# SmartPlug.net
KiCad netlist of a schematic drawn in EAGLE
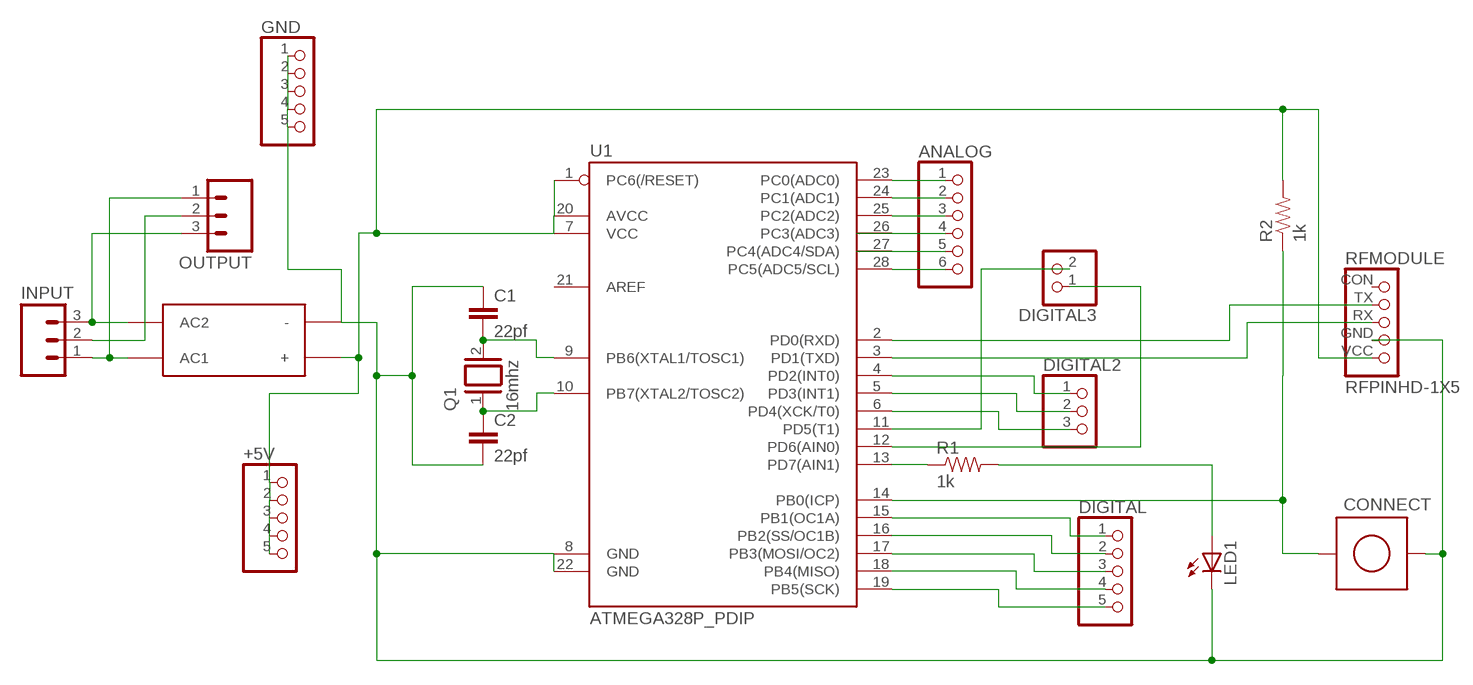
[diagram p0: schematic, sheet 1]

(export (version "E")
  (design (tool "Eeschema 10.0.6"))
  (components
    (comp (ref "+5V")
      (value "PINHD-1X5")
      (footprint "eagle-import:1X05")
      (libsource (lib "eagle-import") (part "PINHD-1X5"))
    )
    (comp (ref "ANALOG")
      (value "PINHD-1X6")
      (footprint "eagle-import:1X06")
      (libsource (lib "eagle-import") (part "PINHD-1X6"))
    )
    (comp (ref "C1")
      (value "22pf")
      (footprint "eagle-import:CAP-PTH-5MM")
      (libsource (lib "eagle-import") (part "CAPPTH1"))
    )
    (comp (ref "C2")
      (value "22pf")
      (footprint "eagle-import:CAP-PTH-5MM")
      (libsource (lib "eagle-import") (part "CAPPTH1"))
    )
    (comp (ref "CONNECT")
      (value "PUSHBUTTON6MM")
      (footprint "eagle-import:PUSHBUTTON6MM")
      (libsource (lib "eagle-import") (part "PUSHBUTTON6MM"))
    )
    (comp (ref "DIGITAL")
      (value "PINHD-1X5")
      (footprint "eagle-import:1X05")
      (libsource (lib "eagle-import") (part "PINHD-1X5"))
    )
    (comp (ref "DIGITAL2")
      (value "PINHD-1X3")
      (footprint "eagle-import:1X03")
      (libsource (lib "eagle-import") (part "PINHD-1X3"))
    )
    (comp (ref "DIGITAL3")
      (value "PINHD-1X2")
      (footprint "eagle-import:1X02")
      (libsource (lib "eagle-import") (part "PINHD-1X2"))
    )
    (comp (ref "GND")
      (value "PINHD-1X5")
      (footprint "eagle-import:1X05")
      (libsource (lib "eagle-import") (part "PINHD-1X5"))
    )
    (comp (ref "INPUT")
      (value "M03-SCREW-5MM")
      (footprint "eagle-import:SCREWTERMINAL-5MM-3")
      (libsource (lib "eagle-import") (part "M03-SCREW-5MM"))
    )
    (comp (ref "LED1")
      (value "LED3MM")
      (footprint "eagle-import:LED3MM")
      (libsource (lib "eagle-import") (part "LED3MM"))
    )
    (comp (ref "OUTPUT")
      (value "M03-SCREW-5MM")
      (footprint "eagle-import:SCREWTERMINAL-5MM-3")
      (libsource (lib "eagle-import") (part "M03-SCREW-5MM"))
    )
    (comp (ref "POWERMODULE")
      (value "POWER_MODULE")
      (footprint "eagle-import:POWER_MODULE")
      (libsource (lib "eagle-import") (part "POWER_MODULE"))
    )
    (comp (ref "Q1")
      (value "16mhz")
      (footprint "eagle-import:QS")
      (libsource (lib "eagle-import") (part "XTAL/S"))
    )
    (comp (ref "R1")
      (value "1k")
      (footprint "eagle-import:1_6W-RES")
      (libsource (lib "eagle-import") (part "RESISTORPTH-1/6W"))
    )
    (comp (ref "R2")
      (value "1k")
      (footprint "eagle-import:1_6W-RES")
      (libsource (lib "eagle-import") (part "RESISTORPTH-1/6W"))
    )
    (comp (ref "RFMODULE")
      (value "RFPINHD-1X5")
      (footprint "eagle-import:1X05")
      (libsource (lib "eagle-import") (part "RFPINHD-1X5"))
    )
    (comp (ref "U1")
      (value "ATMEGA328P_PDIP")
      (footprint "eagle-import:DIL28-3")
      (libsource (lib "eagle-import") (part "ATMEGA328P_PDIP"))
    )
  )
  (nets
    (net (code "1") (name "Net-(INPUT-Pad1)") (class "Default")
      (node (ref "INPUT") (pin "1") (pinfunction "1_1") (pintype "passive"))
      (node (ref "OUTPUT") (pin "1") (pinfunction "1_1") (pintype "passive"))
      (node (ref "POWERMODULE") (pin "AC1") (pinfunction "AC1_AC1") (pintype "bidirectional"))
    )
    (net (code "2") (name "Net-(INPUT-Pad2)") (class "Default")
      (node (ref "INPUT") (pin "2") (pinfunction "2_2") (pintype "passive"))
      (node (ref "OUTPUT") (pin "2") (pinfunction "2_2") (pintype "passive"))
    )
    (net (code "3") (name "Net-(INPUT-Pad3)") (class "Default")
      (node (ref "INPUT") (pin "3") (pinfunction "3_3") (pintype "passive"))
      (node (ref "OUTPUT") (pin "3") (pinfunction "3_3") (pintype "passive"))
      (node (ref "POWERMODULE") (pin "AC2") (pinfunction "AC2_AC2") (pintype "bidirectional"))
    )
    (net (code "4") (name "Net-(LED1-C)") (class "Default")
      (node (ref "C1") (pin "1") (pinfunction "1_1") (pintype "passive"))
      (node (ref "C2") (pin "2") (pinfunction "2_2") (pintype "passive"))
      (node (ref "CONNECT") (pin "P$2") (pinfunction "P$2_P$2") (pintype "output"))
      (node (ref "GND") (pin "1") (pinfunction "1_1") (pintype "passive"))
      (node (ref "GND") (pin "2") (pinfunction "2_2") (pintype "passive"))
      (node (ref "GND") (pin "3") (pinfunction "3_3") (pintype "passive"))
      (node (ref "GND") (pin "4") (pinfunction "4_4") (pintype "passive"))
      (node (ref "GND") (pin "5") (pinfunction "5_5") (pintype "passive"))
      (node (ref "LED1") (pin "K") (pinfunction "C_K") (pintype "passive"))
      (node (ref "POWERMODULE") (pin "-") (pinfunction "-_-") (pintype "bidirectional"))
      (node (ref "RFMODULE") (pin "GND") (pinfunction "4_GND") (pintype "passive"))
      (node (ref "U1") (pin "22") (pinfunction "GND_22") (pintype "bidirectional"))
      (node (ref "U1") (pin "8") (pinfunction "GND_8") (pintype "bidirectional"))
    )
    (net (code "5") (name "Net-(LED1-PadA)") (class "Default")
      (node (ref "LED1") (pin "A") (pinfunction "A_A") (pintype "passive"))
      (node (ref "R1") (pin "2") (pinfunction "2_2") (pintype "passive"))
    )
    (net (code "6") (name "Net-(RFMODULE-2)") (class "Default")
      (node (ref "RFMODULE") (pin "TX") (pinfunction "2_TX") (pintype "passive"))
      (node (ref "U1") (pin "2") (pinfunction "PD0(RXD)_2") (pintype "bidirectional"))
    )
    (net (code "7") (name "Net-(RFMODULE-3)") (class "Default")
      (node (ref "RFMODULE") (pin "RX") (pinfunction "3_RX") (pintype "passive"))
      (node (ref "U1") (pin "3") (pinfunction "PD1(TXD)_3") (pintype "bidirectional"))
    )
    (net (code "8") (name "Net-(RFMODULE-5)") (class "Default")
      (node (ref "+5V") (pin "1") (pinfunction "1_1") (pintype "passive"))
      (node (ref "+5V") (pin "2") (pinfunction "2_2") (pintype "passive"))
      (node (ref "+5V") (pin "3") (pinfunction "3_3") (pintype "passive"))
      (node (ref "+5V") (pin "4") (pinfunction "4_4") (pintype "passive"))
      (node (ref "+5V") (pin "5") (pinfunction "5_5") (pintype "passive"))
      (node (ref "POWERMODULE") (pin "+") (pinfunction "+_+") (pintype "bidirectional"))
      (node (ref "R2") (pin "2") (pinfunction "2_2") (pintype "passive"))
      (node (ref "RFMODULE") (pin "VCC") (pinfunction "5_VCC") (pintype "passive"))
      (node (ref "U1") (pin "1") (pinfunction "PC6(/RESET)_1") (pintype "bidirectional"))
      (node (ref "U1") (pin "20") (pinfunction "AVCC_20") (pintype "bidirectional"))
      (node (ref "U1") (pin "7") (pinfunction "VCC_7") (pintype "bidirectional"))
    )
    (net (code "9") (name "Net-(U1-PB0(ICP))") (class "Default")
      (node (ref "CONNECT") (pin "P$1") (pinfunction "P$1_P$1") (pintype "input"))
      (node (ref "R2") (pin "1") (pinfunction "1_1") (pintype "passive"))
      (node (ref "U1") (pin "14") (pinfunction "PB0(ICP)_14") (pintype "bidirectional"))
    )
    (net (code "10") (name "Net-(U1-PB1(OC1A))") (class "Default")
      (node (ref "DIGITAL") (pin "1") (pinfunction "1_1") (pintype "passive"))
      (node (ref "U1") (pin "15") (pinfunction "PB1(OC1A)_15") (pintype "bidirectional"))
    )
    (net (code "11") (name "Net-(U1-PB2(SS{slash}OC1B))") (class "Default")
      (node (ref "DIGITAL") (pin "2") (pinfunction "2_2") (pintype "passive"))
      (node (ref "U1") (pin "16") (pinfunction "PB2(SS/OC1B)_16") (pintype "bidirectional"))
    )
    (net (code "12") (name "Net-(U1-PB3(MOSI{slash}OC2))") (class "Default")
      (node (ref "DIGITAL") (pin "3") (pinfunction "3_3") (pintype "passive"))
      (node (ref "U1") (pin "17") (pinfunction "PB3(MOSI/OC2)_17") (pintype "bidirectional"))
    )
    (net (code "13") (name "Net-(U1-PB4(MISO))") (class "Default")
      (node (ref "DIGITAL") (pin "4") (pinfunction "4_4") (pintype "passive"))
      (node (ref "U1") (pin "18") (pinfunction "PB4(MISO)_18") (pintype "bidirectional"))
    )
    (net (code "14") (name "Net-(U1-PB5(SCK))") (class "Default")
      (node (ref "DIGITAL") (pin "5") (pinfunction "5_5") (pintype "passive"))
      (node (ref "U1") (pin "19") (pinfunction "PB5(SCK)_19") (pintype "bidirectional"))
    )
    (net (code "15") (name "Net-(U1-PB6(XTAL1{slash}TOSC1))") (class "Default")
      (node (ref "C1") (pin "2") (pinfunction "2_2") (pintype "passive"))
      (node (ref "Q1") (pin "2") (pinfunction "2_2") (pintype "passive"))
      (node (ref "U1") (pin "9") (pinfunction "PB6(XTAL1/TOSC1)_9") (pintype "bidirectional"))
    )
    (net (code "16") (name "Net-(U1-PB7(XTAL2{slash}TOSC2))") (class "Default")
      (node (ref "C2") (pin "1") (pinfunction "1_1") (pintype "passive"))
      (node (ref "Q1") (pin "1") (pinfunction "1_1") (pintype "passive"))
      (node (ref "U1") (pin "10") (pinfunction "PB7(XTAL2/TOSC2)_10") (pintype "bidirectional"))
    )
    (net (code "17") (name "Net-(U1-PC0(ADC0))") (class "Default")
      (node (ref "ANALOG") (pin "1") (pinfunction "1_1") (pintype "passive"))
      (node (ref "U1") (pin "23") (pinfunction "PC0(ADC0)_23") (pintype "bidirectional"))
    )
    (net (code "18") (name "Net-(U1-PC1(ADC1))") (class "Default")
      (node (ref "ANALOG") (pin "2") (pinfunction "2_2") (pintype "passive"))
      (node (ref "U1") (pin "24") (pinfunction "PC1(ADC1)_24") (pintype "bidirectional"))
    )
    (net (code "19") (name "Net-(U1-PC2(ADC2))") (class "Default")
      (node (ref "ANALOG") (pin "3") (pinfunction "3_3") (pintype "passive"))
      (node (ref "U1") (pin "25") (pinfunction "PC2(ADC2)_25") (pintype "bidirectional"))
    )
    (net (code "20") (name "Net-(U1-PC3(ADC3))") (class "Default")
      (node (ref "ANALOG") (pin "4") (pinfunction "4_4") (pintype "passive"))
      (node (ref "U1") (pin "26") (pinfunction "PC3(ADC3)_26") (pintype "bidirectional"))
    )
    (net (code "21") (name "Net-(U1-PC4(ADC4{slash}SDA))") (class "Default")
      (node (ref "ANALOG") (pin "5") (pinfunction "5_5") (pintype "passive"))
      (node (ref "U1") (pin "27") (pinfunction "PC4(ADC4/SDA)_27") (pintype "bidirectional"))
    )
    (net (code "22") (name "Net-(U1-PC5(ADC5{slash}SCL))") (class "Default")
      (node (ref "ANALOG") (pin "6") (pinfunction "6_6") (pintype "passive"))
      (node (ref "U1") (pin "28") (pinfunction "PC5(ADC5/SCL)_28") (pintype "bidirectional"))
    )
    (net (code "23") (name "Net-(U1-PD2(INT0))") (class "Default")
      (node (ref "DIGITAL2") (pin "1") (pinfunction "1_1") (pintype "passive"))
      (node (ref "U1") (pin "4") (pinfunction "PD2(INT0)_4") (pintype "bidirectional"))
    )
    (net (code "24") (name "Net-(U1-PD3(INT1))") (class "Default")
      (node (ref "DIGITAL2") (pin "2") (pinfunction "2_2") (pintype "passive"))
      (node (ref "U1") (pin "5") (pinfunction "PD3(INT1)_5") (pintype "bidirectional"))
    )
    (net (code "25") (name "Net-(U1-PD4(XCK{slash}T0))") (class "Default")
      (node (ref "DIGITAL2") (pin "3") (pinfunction "3_3") (pintype "passive"))
      (node (ref "U1") (pin "6") (pinfunction "PD4(XCK/T0)_6") (pintype "bidirectional"))
    )
    (net (code "26") (name "Net-(U1-PD5(T1))") (class "Default")
      (node (ref "DIGITAL3") (pin "2") (pinfunction "2_2") (pintype "passive"))
      (node (ref "U1") (pin "11") (pinfunction "PD5(T1)_11") (pintype "bidirectional"))
    )
    (net (code "27") (name "Net-(U1-PD6(AIN0))") (class "Default")
      (node (ref "DIGITAL3") (pin "1") (pinfunction "1_1") (pintype "passive"))
      (node (ref "U1") (pin "12") (pinfunction "PD6(AIN0)_12") (pintype "bidirectional"))
    )
    (net (code "28") (name "Net-(U1-PD7(AIN1))") (class "Default")
      (node (ref "R1") (pin "1") (pinfunction "1_1") (pintype "passive"))
      (node (ref "U1") (pin "13") (pinfunction "PD7(AIN1)_13") (pintype "bidirectional"))
    )
    (net (code "29") (name "unconnected-(RFMODULE-1-PadCON)") (class "Default")
      (node (ref "RFMODULE") (pin "CON") (pinfunction "1_CON") (pintype "passive"))
    )
    (net (code "30") (name "unconnected-(U1-AREF-Pad21)") (class "Default")
      (node (ref "U1") (pin "21") (pinfunction "AREF_21") (pintype "bidirectional"))
    )
  )
)
